# F1956.net
KiCad netlist of a schematic drawn in Altium Designer
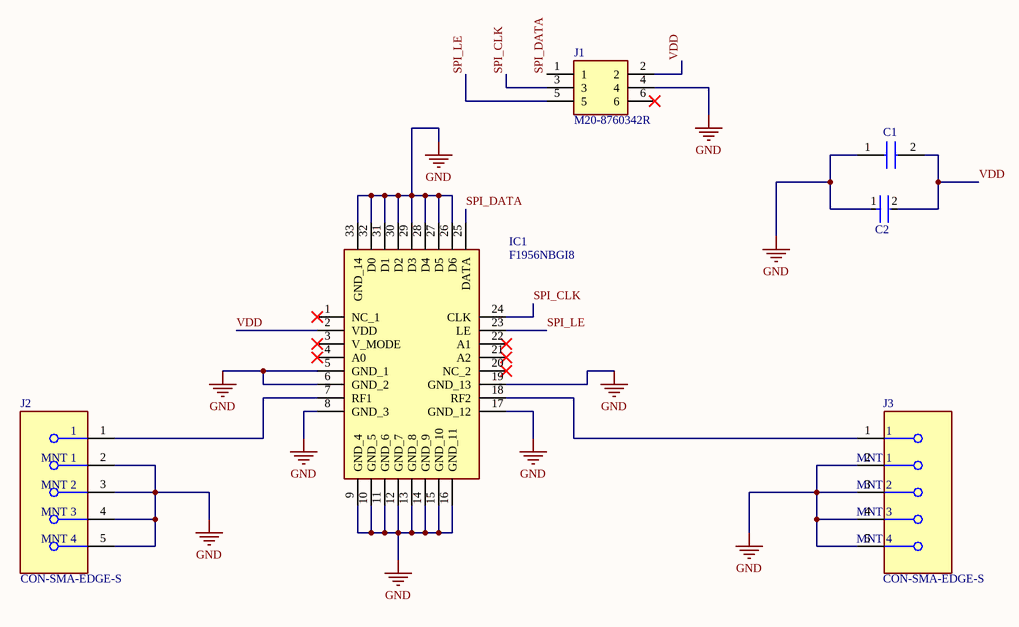
[diagram p0: F1956.SchDoc]

(export (version "E")
  (design (tool "Eeschema 10.0.6"))
  (components
    (comp (ref "C1")
      (value "GJ821BR71H105KA12K")
      (footprint "SamacSys:CAPC2012X135N")
      (description "Capacitor")
      (fields (field (name "MOUSER PART NUMBER") "81-GJ821BR71H105KA2K"))
      (libsource (lib "*") (part "GJ821BR71H105KA12K"))
    )
    (comp (ref "C2")
      (value "GRM21A5C2E102FWA1J")
      (footprint "FP-GRM21A-0_2-MFG")
      (description "Chip Multilayer Ceramic Capacitors for General Purpose, 0805, 1000pF, C0G, 30ppm/°C, 1%, 250V")
      (libsource (lib "Altium Content Vault") (part "02cd4be3c70576c341d710602a673aa"))
    )
    (comp (ref "IC1")
      (value "F1956NBGI8")
      (footprint "SamacSys:QFN50P500X500X80-33N-D")
      (description "Integrated Circuit")
      (fields (field (name "MOUSER PART NUMBER") "972-F1956NBGI8"))
      (libsource (lib "*") (part "F1956NBGI8"))
    )
    (comp (ref "J1")
      (value "M20-8760342R")
      (footprint "SamacSys:M208760342R")
      (description "Connector")
      (fields (field (name "MOUSER PART NUMBER") "855-M20-8760342R"))
      (libsource (lib "*") (part "M20-8760342R"))
    )
    (comp (ref "J2")
      (value "CON-SMA-EDGE-S")
      (footprint "FP-CON-SMA-EDGE-S-MFG")
      (description "CONN SMA JACK STR EDGE MNT")
      (fields
        (field (name "OCTOPART") "https://octopart.com/con-sma-edge-s-rf+solutions-70967450")
        (field (name "MANUFACTURER") "RF Solutions Ltd.")
      )
      (libsource (lib "") (part "a163d97a771fcdd2fd1f1a9264c171f_1"))
    )
    (comp (ref "J3")
      (value "CON-SMA-EDGE-S")
      (footprint "FP-CON-SMA-EDGE-S-MFG")
      (description "CONN SMA JACK STR EDGE MNT")
      (fields
        (field (name "OCTOPART") "https://octopart.com/con-sma-edge-s-rf+solutions-70967450")
        (field (name "MANUFACTURER") "RF Solutions Ltd.")
      )
      (libsource (lib "Altium Content Vault") (part "a163d97a771fcdd2fd1f1a9264c171f"))
    )
  )
  (nets
    (net (code "1") (name "/SPI_CLK") (class "Default")
      (node (ref "IC1") (pin "24") (pinfunction "CLK_24") (pintype "passive"))
      (node (ref "J1") (pin "3") (pinfunction "3_3") (pintype "passive"))
    )
    (net (code "2") (name "/SPI_DATA") (class "Default")
      (node (ref "IC1") (pin "25") (pinfunction "DATA_25") (pintype "passive"))
      (node (ref "J1") (pin "1") (pinfunction "1_1") (pintype "passive"))
    )
    (net (code "3") (name "/SPI_LE") (class "Default")
      (node (ref "IC1") (pin "23") (pinfunction "LE_23") (pintype "passive"))
      (node (ref "J1") (pin "5") (pinfunction "5_5") (pintype "passive"))
    )
    (net (code "4") (name "/VDD") (class "Default")
      (node (ref "C1") (pin "2") (pinfunction "2_2") (pintype "passive"))
      (node (ref "C2") (pin "2") (pinfunction "2_2") (pintype "passive"))
      (node (ref "IC1") (pin "2") (pinfunction "VDD_2") (pintype "passive"))
      (node (ref "J1") (pin "2") (pinfunction "2_2") (pintype "passive"))
    )
    (net (code "5") (name "GND") (class "Default")
      (node (ref "C1") (pin "1") (pinfunction "1_1") (pintype "passive"))
      (node (ref "C2") (pin "1") (pinfunction "1_1") (pintype "passive"))
      (node (ref "IC1") (pin "10") (pinfunction "GND_5_10") (pintype "passive"))
      (node (ref "IC1") (pin "11") (pinfunction "GND_6_11") (pintype "passive"))
      (node (ref "IC1") (pin "12") (pinfunction "GND_7_12") (pintype "passive"))
      (node (ref "IC1") (pin "13") (pinfunction "GND_8_13") (pintype "passive"))
      (node (ref "IC1") (pin "14") (pinfunction "GND_9_14") (pintype "passive"))
      (node (ref "IC1") (pin "15") (pinfunction "GND_10_15") (pintype "passive"))
      (node (ref "IC1") (pin "16") (pinfunction "GND_11_16") (pintype "passive"))
      (node (ref "IC1") (pin "17") (pinfunction "GND_12_17") (pintype "passive"))
      (node (ref "IC1") (pin "19") (pinfunction "GND_13_19") (pintype "passive"))
      (node (ref "IC1") (pin "26") (pinfunction "D6_26") (pintype "passive"))
      (node (ref "IC1") (pin "27") (pinfunction "D5_27") (pintype "passive"))
      (node (ref "IC1") (pin "28") (pinfunction "D4_28") (pintype "passive"))
      (node (ref "IC1") (pin "29") (pinfunction "D3_29") (pintype "passive"))
      (node (ref "IC1") (pin "30") (pinfunction "D2_30") (pintype "passive"))
      (node (ref "IC1") (pin "31") (pinfunction "D1_31") (pintype "passive"))
      (node (ref "IC1") (pin "32") (pinfunction "D0_32") (pintype "passive"))
      (node (ref "IC1") (pin "33") (pinfunction "GND_14_33") (pintype "passive"))
      (node (ref "IC1") (pin "5") (pinfunction "GND_1_5") (pintype "passive"))
      (node (ref "IC1") (pin "6") (pinfunction "GND_2_6") (pintype "passive"))
      (node (ref "IC1") (pin "8") (pinfunction "GND_3_8") (pintype "passive"))
      (node (ref "IC1") (pin "9") (pinfunction "GND_4_9") (pintype "passive"))
      (node (ref "J1") (pin "4") (pinfunction "4_4") (pintype "passive"))
      (node (ref "J2") (pin "2") (pinfunction "MNT_1_2") (pintype "passive"))
      (node (ref "J2") (pin "3") (pinfunction "MNT_2_3") (pintype "passive"))
      (node (ref "J2") (pin "4") (pinfunction "MNT_3_4") (pintype "passive"))
      (node (ref "J2") (pin "5") (pinfunction "MNT_4_5") (pintype "passive"))
      (node (ref "J3") (pin "2") (pinfunction "MNT_1_2") (pintype "passive"))
      (node (ref "J3") (pin "3") (pinfunction "MNT_2_3") (pintype "passive"))
      (node (ref "J3") (pin "4") (pinfunction "MNT_3_4") (pintype "passive"))
      (node (ref "J3") (pin "5") (pinfunction "MNT_4_5") (pintype "passive"))
    )
    (net (code "6") (name "Net-(IC1-RF1)") (class "Default")
      (node (ref "IC1") (pin "7") (pinfunction "RF1_7") (pintype "passive"))
      (node (ref "J2") (pin "1") (pinfunction "1_1") (pintype "passive"))
    )
    (net (code "7") (name "Net-(IC1-RF2)") (class "Default")
      (node (ref "IC1") (pin "18") (pinfunction "RF2_18") (pintype "passive"))
      (node (ref "J3") (pin "1") (pinfunction "1_1") (pintype "passive"))
    )
    (net (code "8") (name "unconnected-(IC1-A0-Pad4)") (class "Default")
      (node (ref "IC1") (pin "4") (pinfunction "A0_4") (pintype "passive+no_connect"))
    )
    (net (code "9") (name "unconnected-(IC1-A1-Pad22)") (class "Default")
      (node (ref "IC1") (pin "22") (pinfunction "A1_22") (pintype "passive+no_connect"))
    )
    (net (code "10") (name "unconnected-(IC1-A2-Pad21)") (class "Default")
      (node (ref "IC1") (pin "21") (pinfunction "A2_21") (pintype "passive+no_connect"))
    )
    (net (code "11") (name "unconnected-(IC1-NC_1-Pad1)") (class "Default")
      (node (ref "IC1") (pin "1") (pinfunction "NC_1_1") (pintype "passive+no_connect"))
    )
    (net (code "12") (name "unconnected-(IC1-NC_2-Pad20)") (class "Default")
      (node (ref "IC1") (pin "20") (pinfunction "NC_2_20") (pintype "passive+no_connect"))
    )
    (net (code "13") (name "unconnected-(IC1-V_MODE-Pad3)") (class "Default")
      (node (ref "IC1") (pin "3") (pinfunction "V_MODE_3") (pintype "passive+no_connect"))
    )
    (net (code "14") (name "unconnected-(J1-Pad6)") (class "Default")
      (node (ref "J1") (pin "6") (pinfunction "6_6") (pintype "passive+no_connect"))
    )
  )
)
